# StepperSMPS.net
KiCad netlist of a schematic drawn in Altium Designer
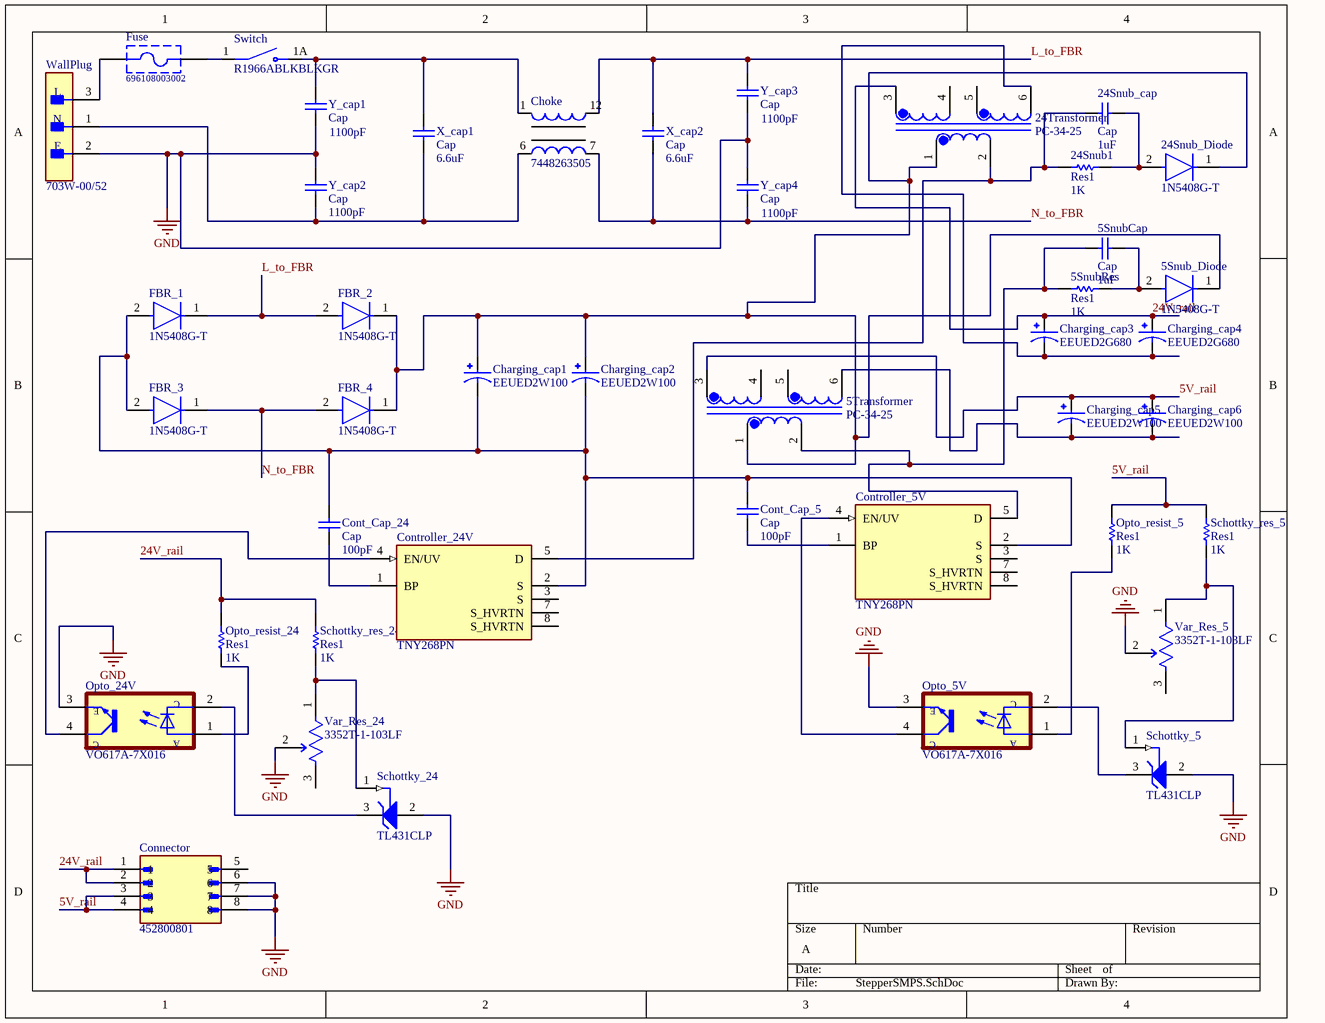
[diagram p0: StepperSMPS.SchDoc]

(export (version "E")
  (design (tool "Eeschema 10.0.6"))
  (components
    (comp (ref "5SnubCap")
      (value "Cap")
      (footprint "RAD-0.3")
      (description "Capacitor")
      (fields (field (name "ALTIUM_VALUE") "1uF") (field (name "PUBLISHER") "Altium Limited"))
      (libsource (lib "Miscellaneous Devices") (part "Cap"))
    )
    (comp (ref "5SnubRes")
      (value "Res1")
      (footprint "AXIAL-0.3")
      (description "Resistor")
      (fields (field (name "ALTIUM_VALUE") "1K") (field (name "PUBLISHER") "Altium Limited"))
      (libsource (lib "Miscellaneous Devices") (part "Res1"))
    )
    (comp (ref "5Snub_Diode")
      (value "1N5408G-T")
      (footprint "FP-DO-201AD-MFG")
      (description "DIODE GEN PURP 1KV 3A DO201AD")
      (libsource (lib "Altium Content Vault") (part "d7152d700b627762746794eb795d46e"))
    )
    (comp (ref "5Transformer")
      (value "PC-34-25")
      (footprint "XFMR_PC-34-25")
      (description "Low Power Miniature Transformer ¦ 1VA Power ¦ 115V Input ¦ 10VCT Output Series")
      (fields (field (name "MF") "{'manufacturer': u'Signal Transformer'}"))
      (libsource (lib "SnapEDA_Library") (part "PC-34-25"))
    )
    (comp (ref "24Snub1")
      (value "Res1")
      (footprint "AXIAL-0.3")
      (description "Resistor")
      (fields (field (name "ALTIUM_VALUE") "1K") (field (name "PUBLISHER") "Altium Limited"))
      (libsource (lib "Miscellaneous Devices") (part "Res1"))
    )
    (comp (ref "24Snub_cap")
      (value "Cap")
      (footprint "RAD-0.3")
      (description "Capacitor")
      (fields (field (name "ALTIUM_VALUE") "1uF") (field (name "PUBLISHER") "Altium Limited"))
      (libsource (lib "Miscellaneous Devices") (part "Cap"))
    )
    (comp (ref "24Snub_Diode")
      (value "1N5408G-T")
      (footprint "FP-DO-201AD-MFG")
      (description "DIODE GEN PURP 1KV 3A DO201AD")
      (libsource (lib "Altium Content Vault") (part "d7152d700b627762746794eb795d46e"))
    )
    (comp (ref "24Transformer")
      (value "PC-34-25")
      (footprint "XFMR_PC-34-25")
      (description "Low Power Miniature Transformer ¦ 1VA Power ¦ 115V Input ¦ 10VCT Output Series")
      (fields (field (name "MF") "{'manufacturer': u'Signal Transformer'}"))
      (libsource (lib "SnapEDA_Library") (part "PC-34-25"))
    )
    (comp (ref "Charging_cap1")
      (value "EEUED2W100")
      (footprint "CAPPRD500W60D1250H2000")
      (description "ED-A")
      (fields (field (name "MF") "{'manufacturer': u'Panasonic Electronic'}"))
      (libsource (lib "SnapEDA_Library") (part "EEUED2W100"))
    )
    (comp (ref "Charging_cap2")
      (value "EEUED2W100")
      (footprint "CAPPRD500W60D1250H2000")
      (description "ED-A")
      (fields (field (name "MF") "{'manufacturer': u'Panasonic Electronic'}"))
      (libsource (lib "SnapEDA_Library") (part "EEUED2W100"))
    )
    (comp (ref "Charging_cap3")
      (value "EEUED2G680")
      (footprint "CAPPRD750W80D1800H3150")
      (description "ED-A")
      (fields (field (name "MF") "{'manufacturer': u'Panasonic'}"))
      (libsource (lib "SnapEDA_Library") (part "EEUED2G680"))
    )
    (comp (ref "Charging_cap4")
      (value "EEUED2G680")
      (footprint "CAPPRD750W80D1800H3150")
      (description "ED-A")
      (fields (field (name "MF") "{'manufacturer': u'Panasonic'}"))
      (libsource (lib "SnapEDA_Library") (part "EEUED2G680"))
    )
    (comp (ref "Charging_cap5")
      (value "EEUED2W100")
      (footprint "CAPPRD500W60D1250H2000")
      (description "ED-A")
      (fields (field (name "MF") "{'manufacturer': u'Panasonic Electronic'}"))
      (libsource (lib "SnapEDA_Library") (part "EEUED2W100"))
    )
    (comp (ref "Charging_cap6")
      (value "EEUED2W100")
      (footprint "CAPPRD500W60D1250H2000")
      (description "ED-A")
      (fields (field (name "MF") "{'manufacturer': u'Panasonic Electronic'}"))
      (libsource (lib "SnapEDA_Library") (part "EEUED2W100"))
    )
    (comp (ref "Choke")
      (value "7448263505")
      (footprint "WE-CMB-XXL")
      (description "THT Common Mode Power Line Choke WE-CMB, L = 0.50 mH")
      (libsource (lib "Altium Content Vault") (part "PAS-IND-INDUCTOR-4G"))
    )
    (comp (ref "Connector")
      (value "452800801")
      (footprint "45280-0801:MOLEX_452800801")
      (fields (field (name "MF") "{'manufacturer': u'Molex'}"))
      (libsource (lib "*") (part "452800801"))
    )
    (comp (ref "Controller_5V")
      (value "TNY268PN")
      (footprint "DIP762W46P254L957H406Q7")
      (description "Converter Offline Flyback Topology 132kHz DIP-8B")
      (fields (field (name "MF") "{'manufacturer': u'Power Integrations'}"))
      (libsource (lib "SnapEDA_Library") (part "TNY268PN"))
    )
    (comp (ref "Controller_24V")
      (value "TNY268PN")
      (footprint "DIP762W46P254L957H406Q7")
      (description "Converter Offline Flyback Topology 132kHz DIP-8B")
      (fields (field (name "MF") "{'manufacturer': u'Power Integrations'}"))
      (libsource (lib "SnapEDA_Library") (part "TNY268PN"))
    )
    (comp (ref "Cont_Cap_5")
      (value "Cap")
      (footprint "RAD-0.3")
      (description "Capacitor")
      (fields (field (name "ALTIUM_VALUE") "100pF") (field (name "PUBLISHER") "Altium Limited"))
      (libsource (lib "Miscellaneous Devices") (part "Cap"))
    )
    (comp (ref "Cont_Cap_24")
      (value "Cap")
      (footprint "RAD-0.3")
      (description "Capacitor")
      (fields (field (name "ALTIUM_VALUE") "100pF") (field (name "PUBLISHER") "Altium Limited"))
      (libsource (lib "Miscellaneous Devices") (part "Cap"))
    )
    (comp (ref "FBR_1")
      (value "1N5408G-T")
      (footprint "FP-DO-201AD-MFG")
      (description "DIODE GEN PURP 1KV 3A DO201AD")
      (libsource (lib "Altium Content Vault") (part "d7152d700b627762746794eb795d46e"))
    )
    (comp (ref "FBR_2")
      (value "1N5408G-T")
      (footprint "FP-DO-201AD-MFG")
      (description "DIODE GEN PURP 1KV 3A DO201AD")
      (libsource (lib "Altium Content Vault") (part "d7152d700b627762746794eb795d46e"))
    )
    (comp (ref "FBR_3")
      (value "1N5408G-T")
      (footprint "FP-DO-201AD-MFG")
      (description "DIODE GEN PURP 1KV 3A DO201AD")
      (libsource (lib "Altium Content Vault") (part "d7152d700b627762746794eb795d46e"))
    )
    (comp (ref "FBR_4")
      (value "1N5408G-T")
      (footprint "FP-DO-201AD-MFG")
      (description "DIODE GEN PURP 1KV 3A DO201AD")
      (libsource (lib "Altium Content Vault") (part "d7152d700b627762746794eb795d46e"))
    )
    (comp (ref "Fuse")
      (value "696108003002")
      (footprint "696108003002")
      (description "WR-FSH Fuse Holder Blocks Fuse Holder Blocks Clip Cover for PCB")
      (fields (field (name "MANUFACTURER") "Wurth Elektronik") (field (name "PUBLISHER") "WurthElektronik"))
      (libsource (lib "Altium Content Vault") (part "WE-FUSE-2"))
    )
    (comp (ref "Opto_5V")
      (value "VO617A-7X016")
      (footprint "DIP1016W50P254L458H480Q4")
      (fields (field (name "MF") "{'manufacturer': u'Vishay'}"))
      (libsource (lib "SnapEDA_Library") (part "VO617A-7X016"))
    )
    (comp (ref "Opto_24V")
      (value "VO617A-7X016")
      (footprint "DIP1016W50P254L458H480Q4")
      (fields (field (name "MF") "{'manufacturer': u'Vishay'}"))
      (libsource (lib "SnapEDA_Library") (part "VO617A-7X016"))
    )
    (comp (ref "Opto_resist_5")
      (value "Res1")
      (footprint "AXIAL-0.3")
      (description "Resistor")
      (fields (field (name "ALTIUM_VALUE") "1K") (field (name "PUBLISHER") "Altium Limited"))
      (libsource (lib "Miscellaneous Devices") (part "Res1"))
    )
    (comp (ref "Opto_resist_24")
      (value "Res1")
      (footprint "AXIAL-0.3")
      (description "Resistor")
      (fields (field (name "ALTIUM_VALUE") "1K") (field (name "PUBLISHER") "Altium Limited"))
      (libsource (lib "Miscellaneous Devices") (part "Res1"))
    )
    (comp (ref "Schottky_5")
      (value "TL431CLP")
      (footprint "LP0003A")
      (fields (field (name "MANUFACTURER") "Texas Instruments"))
      (libsource (lib "Altium Content Vault") (part "TI-TL431LP3"))
    )
    (comp (ref "Schottky_24")
      (value "TL431CLP")
      (footprint "LP0003A")
      (fields (field (name "MANUFACTURER") "Texas Instruments"))
      (libsource (lib "Altium Content Vault") (part "TI-TL431LP3"))
    )
    (comp (ref "Schottky_res_5")
      (value "Res1")
      (footprint "AXIAL-0.3")
      (description "Resistor")
      (fields (field (name "ALTIUM_VALUE") "1K") (field (name "PUBLISHER") "Altium Limited"))
      (libsource (lib "Miscellaneous Devices") (part "Res1"))
    )
    (comp (ref "Schottky_res_24")
      (value "Res1")
      (footprint "AXIAL-0.3")
      (description "Resistor")
      (fields (field (name "ALTIUM_VALUE") "1K") (field (name "PUBLISHER") "Altium Limited"))
      (libsource (lib "Miscellaneous Devices") (part "Res1"))
    )
    (comp (ref "Switch")
      (value "R1966ABLKBLKGR")
      (footprint "SW_R1966ABLKBLKGR")
      (fields (field (name "MF") "{'manufacturer': u'E-Switch'}"))
      (libsource (lib "SnapEDA_Library") (part "R1966ABLKBLKGR"))
    )
    (comp (ref "Var_Res_5")
      (value "3352T-1-103LF")
      (footprint "FP-3352T-MFG")
      (description "THUMBWHEEL POT 10K OHM 0.5W TOP")
      (fields (field (name "TOLERANCE") "20%"))
      (libsource (lib "Altium Content Vault") (part "2dcfd2547301a7d3209a5e99acfd772"))
    )
    (comp (ref "Var_Res_24")
      (value "3352T-1-103LF")
      (footprint "FP-3352T-MFG")
      (description "THUMBWHEEL POT 10K OHM 0.5W TOP")
      (fields (field (name "TOLERANCE") "20%"))
      (libsource (lib "Altium Content Vault") (part "2dcfd2547301a7d3209a5e99acfd772"))
    )
    (comp (ref "WallPlug")
      (value "703W-00/52")
      (footprint "FP-703W-00-52-MFG")
      (description "PWR ENT RCPT IEC320-C14 PNL SLDR")
      (libsource (lib "Altium Content Vault") (part "d3fa5aafac2488dd744475722bda3d4"))
    )
    (comp (ref "X_cap1")
      (value "Cap")
      (footprint "RAD-0.3")
      (description "Capacitor")
      (fields (field (name "ALTIUM_VALUE") "6.6uF") (field (name "PUBLISHER") "Altium Limited"))
      (libsource (lib "Miscellaneous Devices") (part "Cap"))
    )
    (comp (ref "X_cap2")
      (value "Cap")
      (footprint "RAD-0.3")
      (description "Capacitor")
      (fields (field (name "ALTIUM_VALUE") "6.6uF") (field (name "PUBLISHER") "Altium Limited"))
      (libsource (lib "Miscellaneous Devices") (part "Cap"))
    )
    (comp (ref "Y_cap1")
      (value "Cap")
      (footprint "RAD-0.3")
      (description "Capacitor")
      (fields (field (name "ALTIUM_VALUE") "1100pF") (field (name "PUBLISHER") "Altium Limited"))
      (libsource (lib "Miscellaneous Devices") (part "Cap"))
    )
    (comp (ref "Y_cap2")
      (value "Cap")
      (footprint "RAD-0.3")
      (description "Capacitor")
      (fields (field (name "ALTIUM_VALUE") "1100pF") (field (name "PUBLISHER") "Altium Limited"))
      (libsource (lib "Miscellaneous Devices") (part "Cap"))
    )
    (comp (ref "Y_cap3")
      (value "Cap")
      (footprint "RAD-0.3")
      (description "Capacitor")
      (fields (field (name "ALTIUM_VALUE") "1100pF") (field (name "PUBLISHER") "Altium Limited"))
      (libsource (lib "Miscellaneous Devices") (part "Cap"))
    )
    (comp (ref "Y_cap4")
      (value "Cap")
      (footprint "RAD-0.3")
      (description "Capacitor")
      (fields (field (name "ALTIUM_VALUE") "1100pF") (field (name "PUBLISHER") "Altium Limited"))
      (libsource (lib "Miscellaneous Devices") (part "Cap"))
    )
  )
  (nets
    (net (code "1") (name "/5V_rail") (class "Default")
      (node (ref "5Transformer") (pin "3") (pinfunction "3_3") (pintype "passive"))
      (node (ref "Charging_cap5") (pin "P") (pinfunction "P_P") (pintype "passive"))
      (node (ref "Charging_cap6") (pin "P") (pinfunction "P_P") (pintype "passive"))
      (node (ref "Connector") (pin "3") (pinfunction "3_3") (pintype "passive"))
      (node (ref "Connector") (pin "4") (pinfunction "4_4") (pintype "passive"))
      (node (ref "Opto_resist_5") (pin "2") (pinfunction "2_2") (pintype "passive"))
      (node (ref "Schottky_res_5") (pin "2") (pinfunction "2_2") (pintype "passive"))
    )
    (net (code "2") (name "/24V_rail") (class "Default")
      (node (ref "24Transformer") (pin "3") (pinfunction "3_3") (pintype "passive"))
      (node (ref "Charging_cap3") (pin "P") (pinfunction "P_P") (pintype "passive"))
      (node (ref "Charging_cap4") (pin "P") (pinfunction "P_P") (pintype "passive"))
      (node (ref "Connector") (pin "1") (pinfunction "1_1") (pintype "passive"))
      (node (ref "Connector") (pin "2") (pinfunction "2_2") (pintype "passive"))
      (node (ref "Opto_resist_24") (pin "2") (pinfunction "2_2") (pintype "passive"))
      (node (ref "Schottky_res_24") (pin "2") (pinfunction "2_2") (pintype "passive"))
    )
    (net (code "3") (name "/L_to_FBR") (class "Default")
      (node (ref "Choke") (pin "12") (pinfunction "12_12") (pintype "passive"))
      (node (ref "FBR_1") (pin "1") (pinfunction "C_1") (pintype "passive"))
      (node (ref "FBR_2") (pin "2") (pinfunction "A_2") (pintype "passive"))
      (node (ref "X_cap2") (pin "2") (pinfunction "2_2") (pintype "passive"))
      (node (ref "Y_cap3") (pin "2") (pinfunction "2_2") (pintype "passive"))
    )
    (net (code "4") (name "/N_to_FBR") (class "Default")
      (node (ref "Choke") (pin "7") (pinfunction "7_7") (pintype "passive"))
      (node (ref "FBR_3") (pin "1") (pinfunction "C_1") (pintype "passive"))
      (node (ref "FBR_4") (pin "2") (pinfunction "A_2") (pintype "passive"))
      (node (ref "X_cap2") (pin "1") (pinfunction "1_1") (pintype "passive"))
      (node (ref "Y_cap4") (pin "1") (pinfunction "1_1") (pintype "passive"))
    )
    (net (code "5") (name "GND") (class "Default")
      (node (ref "Connector") (pin "6") (pinfunction "6_6") (pintype "passive"))
      (node (ref "Connector") (pin "7") (pinfunction "7_7") (pintype "passive"))
      (node (ref "Connector") (pin "8") (pinfunction "8_8") (pintype "passive"))
      (node (ref "Opto_24V") (pin "3") (pinfunction "E_3") (pintype "passive"))
      (node (ref "Opto_5V") (pin "3") (pinfunction "E_3") (pintype "passive"))
      (node (ref "Schottky_24") (pin "2") (pinfunction "ANODE_2") (pintype "passive"))
      (node (ref "Schottky_5") (pin "2") (pinfunction "ANODE_2") (pintype "passive"))
      (node (ref "Var_Res_24") (pin "2") (pinfunction "WIPER_2") (pintype "passive"))
      (node (ref "Var_Res_5") (pin "2") (pinfunction "WIPER_2") (pintype "passive"))
      (node (ref "WallPlug") (pin "2") (pinfunction "E_2") (pintype "passive"))
      (node (ref "Y_cap1") (pin "1") (pinfunction "1_1") (pintype "passive"))
      (node (ref "Y_cap2") (pin "2") (pinfunction "2_2") (pintype "passive"))
      (node (ref "Y_cap3") (pin "1") (pinfunction "1_1") (pintype "passive"))
      (node (ref "Y_cap4") (pin "2") (pinfunction "2_2") (pintype "passive"))
    )
    (net (code "6") (name "Net-(5Snub_Diode-A)") (class "Default")
      (node (ref "5SnubCap") (pin "1") (pinfunction "1_1") (pintype "passive"))
      (node (ref "5SnubRes") (pin "1") (pinfunction "1_1") (pintype "passive"))
      (node (ref "5Snub_Diode") (pin "2") (pinfunction "A_2") (pintype "passive"))
    )
    (net (code "7") (name "Net-(5Transformer-Pad6)") (class "Default")
      (node (ref "5Transformer") (pin "6") (pinfunction "6_6") (pintype "passive"))
      (node (ref "Charging_cap5") (pin "N") (pinfunction "N_N") (pintype "passive"))
      (node (ref "Charging_cap6") (pin "N") (pinfunction "N_N") (pintype "passive"))
    )
    (net (code "8") (name "Net-(24Snub_Diode-A)") (class "Default")
      (node (ref "24Snub1") (pin "1") (pinfunction "1_1") (pintype "passive"))
      (node (ref "24Snub_Diode") (pin "2") (pinfunction "A_2") (pintype "passive"))
      (node (ref "24Snub_cap") (pin "1") (pinfunction "1_1") (pintype "passive"))
    )
    (net (code "9") (name "Net-(24Snub_Diode-C)") (class "Default")
      (node (ref "24Snub_Diode") (pin "1") (pinfunction "C_1") (pintype "passive"))
      (node (ref "24Transformer") (pin "1") (pinfunction "1_1") (pintype "passive"))
      (node (ref "5Snub_Diode") (pin "1") (pinfunction "C_1") (pintype "passive"))
      (node (ref "5Transformer") (pin "1") (pinfunction "1_1") (pintype "passive"))
      (node (ref "Charging_cap1") (pin "P") (pinfunction "P_P") (pintype "passive"))
      (node (ref "Charging_cap2") (pin "P") (pinfunction "P_P") (pintype "passive"))
      (node (ref "FBR_2") (pin "1") (pinfunction "C_1") (pintype "passive"))
      (node (ref "FBR_4") (pin "1") (pinfunction "C_1") (pintype "passive"))
    )
    (net (code "10") (name "Net-(24Transformer-Pad6)") (class "Default")
      (node (ref "24Transformer") (pin "6") (pinfunction "6_6") (pintype "passive"))
      (node (ref "Charging_cap3") (pin "N") (pinfunction "N_N") (pintype "passive"))
      (node (ref "Charging_cap4") (pin "N") (pinfunction "N_N") (pintype "passive"))
    )
    (net (code "11") (name "Net-(Choke-Pad1)") (class "Default")
      (node (ref "Choke") (pin "1") (pinfunction "1_1") (pintype "passive"))
      (node (ref "Switch") (pin "1A") (pinfunction "1A_1A") (pintype "passive"))
      (node (ref "X_cap1") (pin "2") (pinfunction "2_2") (pintype "passive"))
      (node (ref "Y_cap1") (pin "2") (pinfunction "2_2") (pintype "passive"))
    )
    (net (code "12") (name "Net-(Controller_5V-BP)") (class "Default")
      (node (ref "Cont_Cap_5") (pin "1") (pinfunction "1_1") (pintype "passive"))
      (node (ref "Controller_5V") (pin "1") (pinfunction "BP_1") (pintype "passive"))
    )
    (net (code "13") (name "Net-(Controller_5V-D)") (class "Default")
      (node (ref "5SnubCap") (pin "2") (pinfunction "2_2") (pintype "passive"))
      (node (ref "5SnubRes") (pin "2") (pinfunction "2_2") (pintype "passive"))
      (node (ref "5Transformer") (pin "2") (pinfunction "2_2") (pintype "passive"))
      (node (ref "Controller_5V") (pin "5") (pinfunction "D_5") (pintype "passive"))
    )
    (net (code "14") (name "Net-(Controller_5V-EN{slash}UV)") (class "Default")
      (node (ref "Controller_5V") (pin "4") (pinfunction "EN/UV_4") (pintype "input"))
      (node (ref "Opto_5V") (pin "4") (pinfunction "CO_4") (pintype "passive"))
    )
    (net (code "15") (name "Net-(Controller_24V-BP)") (class "Default")
      (node (ref "Cont_Cap_24") (pin "1") (pinfunction "1_1") (pintype "passive"))
      (node (ref "Controller_24V") (pin "1") (pinfunction "BP_1") (pintype "passive"))
    )
    (net (code "16") (name "Net-(Controller_24V-D)") (class "Default")
      (node (ref "24Snub1") (pin "2") (pinfunction "2_2") (pintype "passive"))
      (node (ref "24Snub_cap") (pin "2") (pinfunction "2_2") (pintype "passive"))
      (node (ref "24Transformer") (pin "2") (pinfunction "2_2") (pintype "passive"))
      (node (ref "Controller_24V") (pin "5") (pinfunction "D_5") (pintype "passive"))
    )
    (net (code "17") (name "Net-(Controller_24V-EN{slash}UV)") (class "Default")
      (node (ref "Controller_24V") (pin "4") (pinfunction "EN/UV_4") (pintype "input"))
      (node (ref "Opto_24V") (pin "4") (pinfunction "CO_4") (pintype "passive"))
    )
    (net (code "18") (name "Net-(FBR_1-A)") (class "Default")
      (node (ref "Charging_cap1") (pin "N") (pinfunction "N_N") (pintype "passive"))
      (node (ref "Charging_cap2") (pin "N") (pinfunction "N_N") (pintype "passive"))
      (node (ref "Cont_Cap_24") (pin "2") (pinfunction "2_2") (pintype "passive"))
      (node (ref "Cont_Cap_5") (pin "2") (pinfunction "2_2") (pintype "passive"))
      (node (ref "Controller_24V") (pin "2") (pinfunction "S_2") (pintype "passive"))
      (node (ref "Controller_5V") (pin "2") (pinfunction "S_2") (pintype "passive"))
      (node (ref "FBR_1") (pin "2") (pinfunction "A_2") (pintype "passive"))
      (node (ref "FBR_3") (pin "2") (pinfunction "A_2") (pintype "passive"))
    )
    (net (code "19") (name "Net-(Fuse-Pad2)") (class "Default")
      (node (ref "Fuse") (pin "2") (pinfunction "2_2") (pintype "passive"))
      (node (ref "Switch") (pin "1") (pinfunction "1_1") (pintype "passive"))
    )
    (net (code "20") (name "Net-(Opto_5V-A)") (class "Default")
      (node (ref "Opto_5V") (pin "1") (pinfunction "A_1") (pintype "passive"))
      (node (ref "Opto_resist_5") (pin "1") (pinfunction "1_1") (pintype "passive"))
    )
    (net (code "21") (name "Net-(Opto_5V-C)") (class "Default")
      (node (ref "Opto_5V") (pin "2") (pinfunction "C_2") (pintype "passive"))
      (node (ref "Schottky_5") (pin "3") (pinfunction "CATHODE_3") (pintype "passive"))
    )
    (net (code "22") (name "Net-(Opto_24V-A)") (class "Default")
      (node (ref "Opto_24V") (pin "1") (pinfunction "A_1") (pintype "passive"))
      (node (ref "Opto_resist_24") (pin "1") (pinfunction "1_1") (pintype "passive"))
    )
    (net (code "23") (name "Net-(Opto_24V-C)") (class "Default")
      (node (ref "Opto_24V") (pin "2") (pinfunction "C_2") (pintype "passive"))
      (node (ref "Schottky_24") (pin "3") (pinfunction "CATHODE_3") (pintype "passive"))
    )
    (net (code "24") (name "Net-(Schottky_5-REF)") (class "Default")
      (node (ref "Schottky_5") (pin "1") (pinfunction "REF_1") (pintype "input"))
      (node (ref "Schottky_res_5") (pin "1") (pinfunction "1_1") (pintype "passive"))
      (node (ref "Var_Res_5") (pin "1") (pinfunction "CCW_1") (pintype "passive"))
    )
    (net (code "25") (name "Net-(Schottky_24-REF)") (class "Default")
      (node (ref "Schottky_24") (pin "1") (pinfunction "REF_1") (pintype "input"))
      (node (ref "Schottky_res_24") (pin "1") (pinfunction "1_1") (pintype "passive"))
      (node (ref "Var_Res_24") (pin "1") (pinfunction "CCW_1") (pintype "passive"))
    )
    (net (code "26") (name "Net-(WallPlug-L)") (class "Default")
      (node (ref "Fuse") (pin "1") (pinfunction "1_1") (pintype "passive"))
      (node (ref "WallPlug") (pin "3") (pinfunction "L_3") (pintype "passive"))
    )
    (net (code "27") (name "Net-(WallPlug-N)") (class "Default")
      (node (ref "Choke") (pin "6") (pinfunction "6_6") (pintype "passive"))
      (node (ref "WallPlug") (pin "1") (pinfunction "N_1") (pintype "passive"))
      (node (ref "X_cap1") (pin "1") (pinfunction "1_1") (pintype "passive"))
      (node (ref "Y_cap2") (pin "1") (pinfunction "1_1") (pintype "passive"))
    )
    (net (code "28") (name "unconnected-(5Transformer-Pad4)") (class "Default")
      (node (ref "5Transformer") (pin "4") (pinfunction "4_4") (pintype "passive"))
    )
    (net (code "29") (name "unconnected-(5Transformer-Pad5)") (class "Default")
      (node (ref "5Transformer") (pin "5") (pinfunction "5_5") (pintype "passive"))
    )
    (net (code "30") (name "unconnected-(24Transformer-Pad4)") (class "Default")
      (node (ref "24Transformer") (pin "4") (pinfunction "4_4") (pintype "passive"))
    )
    (net (code "31") (name "unconnected-(24Transformer-Pad5)") (class "Default")
      (node (ref "24Transformer") (pin "5") (pinfunction "5_5") (pintype "passive"))
    )
    (net (code "32") (name "unconnected-(Connector-Pad5)") (class "Default")
      (node (ref "Connector") (pin "5") (pinfunction "5_5") (pintype "passive"))
    )
    (net (code "33") (name "unconnected-(Controller_5V-S-Pad3)") (class "Default")
      (node (ref "Controller_5V") (pin "3") (pinfunction "S_3") (pintype "passive"))
    )
    (net (code "34") (name "unconnected-(Controller_5V-S_HVRTN-Pad7)") (class "Default")
      (node (ref "Controller_5V") (pin "7") (pinfunction "S_HVRTN_7") (pintype "passive"))
    )
    (net (code "35") (name "unconnected-(Controller_5V-S_HVRTN-Pad8)") (class "Default")
      (node (ref "Controller_5V") (pin "8") (pinfunction "S_HVRTN_8") (pintype "passive"))
    )
    (net (code "36") (name "unconnected-(Controller_24V-S-Pad3)") (class "Default")
      (node (ref "Controller_24V") (pin "3") (pinfunction "S_3") (pintype "passive"))
    )
    (net (code "37") (name "unconnected-(Controller_24V-S_HVRTN-Pad7)") (class "Default")
      (node (ref "Controller_24V") (pin "7") (pinfunction "S_HVRTN_7") (pintype "passive"))
    )
    (net (code "38") (name "unconnected-(Controller_24V-S_HVRTN-Pad8)") (class "Default")
      (node (ref "Controller_24V") (pin "8") (pinfunction "S_HVRTN_8") (pintype "passive"))
    )
    (net (code "39") (name "unconnected-(Var_Res_5-CW-Pad3)") (class "Default")
      (node (ref "Var_Res_5") (pin "3") (pinfunction "CW_3") (pintype "passive"))
    )
    (net (code "40") (name "unconnected-(Var_Res_24-CW-Pad3)") (class "Default")
      (node (ref "Var_Res_24") (pin "3") (pinfunction "CW_3") (pintype "passive"))
    )
  )
)
